# 640mk6.net
KiCad netlist of a schematic drawn in EAGLE
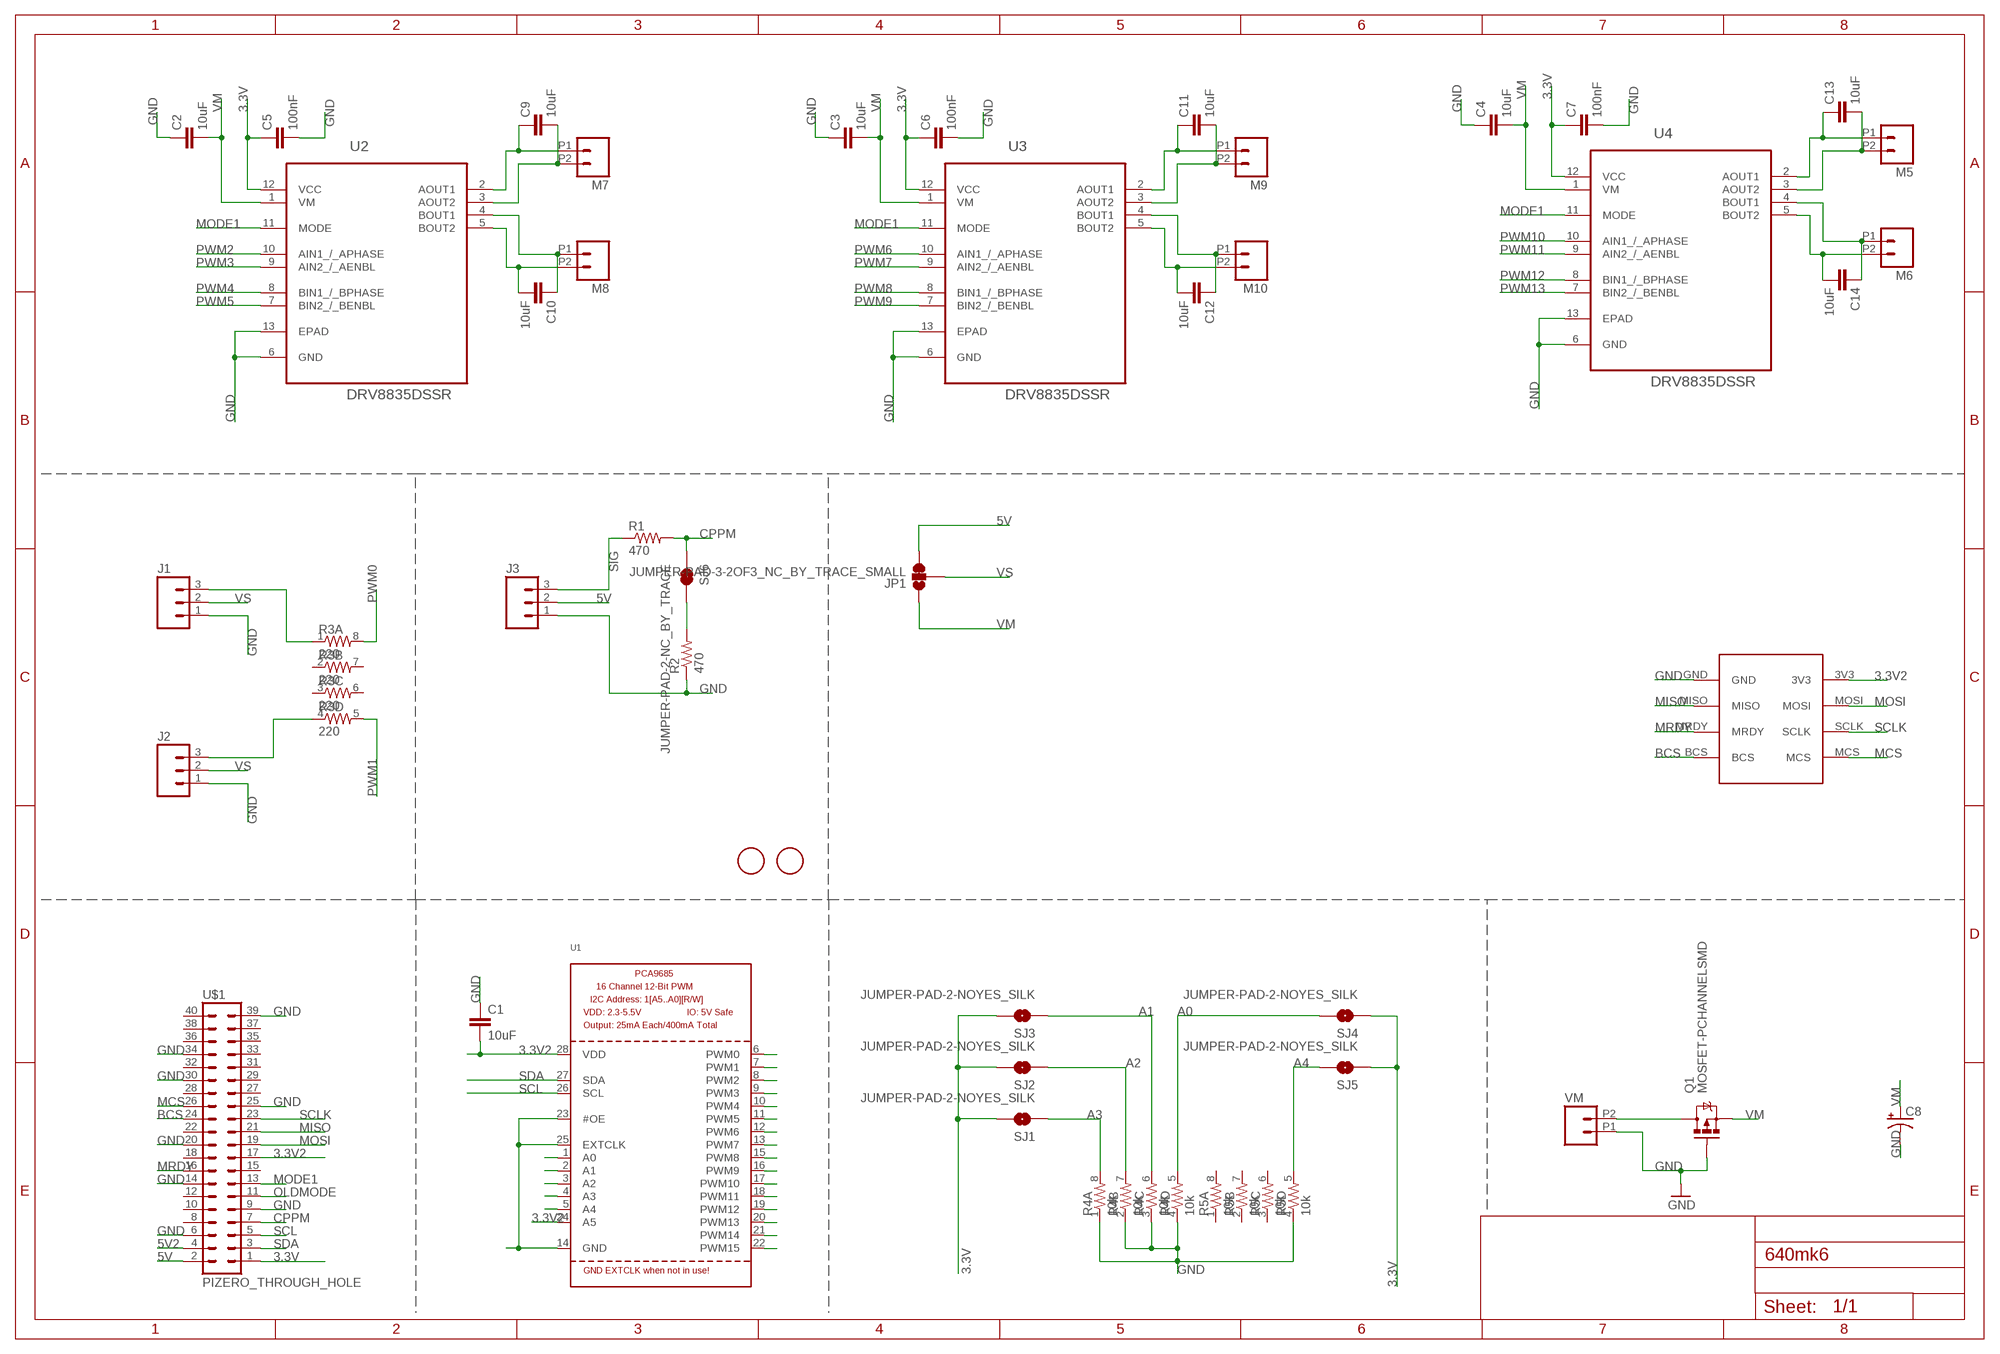
[diagram p0: schematic, sheet 1]

(export (version "E")
  (design (tool "Eeschema 10.0.6"))
  (components
    (comp (ref "C1")
      (value "10uF")
      (footprint "eagle-import:0805")
      (libsource (lib "eagle-import") (part "CAP0805"))
    )
    (comp (ref "C2")
      (value "10uF")
      (footprint "eagle-import:0805")
      (libsource (lib "eagle-import") (part "CAP0805"))
    )
    (comp (ref "C3")
      (value "10uF")
      (footprint "eagle-import:0805")
      (libsource (lib "eagle-import") (part "CAP0805"))
    )
    (comp (ref "C4")
      (value "10uF")
      (footprint "eagle-import:0805")
      (libsource (lib "eagle-import") (part "CAP0805"))
    )
    (comp (ref "C5")
      (value "100nF")
      (footprint "eagle-import:0805")
      (libsource (lib "eagle-import") (part "CAP0805"))
    )
    (comp (ref "C6")
      (value "100nF")
      (footprint "eagle-import:0805")
      (libsource (lib "eagle-import") (part "CAP0805"))
    )
    (comp (ref "C7")
      (value "100nF")
      (footprint "eagle-import:0805")
      (libsource (lib "eagle-import") (part "CAP0805"))
    )
    (comp (ref "C8")
      (value "CAP_POLPTH1")
      (footprint "eagle-import:CPOL-RADIAL-100UF-25V")
      (libsource (lib "eagle-import") (part "CAP_POLPTH1"))
    )
    (comp (ref "C9")
      (value "10uF")
      (footprint "eagle-import:0805")
      (libsource (lib "eagle-import") (part "CAP0805"))
    )
    (comp (ref "C10")
      (value "10uF")
      (footprint "eagle-import:0805")
      (libsource (lib "eagle-import") (part "CAP0805"))
    )
    (comp (ref "C11")
      (value "10uF")
      (footprint "eagle-import:0805")
      (libsource (lib "eagle-import") (part "CAP0805"))
    )
    (comp (ref "C12")
      (value "10uF")
      (footprint "eagle-import:0805")
      (libsource (lib "eagle-import") (part "CAP0805"))
    )
    (comp (ref "C13")
      (value "10uF")
      (footprint "eagle-import:0805")
      (libsource (lib "eagle-import") (part "CAP0805"))
    )
    (comp (ref "C14")
      (value "10uF")
      (footprint "eagle-import:0805")
      (libsource (lib "eagle-import") (part "CAP0805"))
    )
    (comp (ref "FID1")
      (value "FIDUCIAL")
      (footprint "eagle-import:FIDUCIAL_1MM")
      (libsource (lib "eagle-import") (part "FIDUCIAL"))
    )
    (comp (ref "FID2")
      (value "FIDUCIAL")
      (footprint "eagle-import:FIDUCIAL_1MM")
      (libsource (lib "eagle-import") (part "FIDUCIAL"))
    )
    (comp (ref "J1")
      (value "M03LOCK")
      (footprint "eagle-import:1X03_LOCK")
      (libsource (lib "eagle-import") (part "M03LOCK"))
    )
    (comp (ref "J2")
      (value "M03LOCK")
      (footprint "eagle-import:1X03_LOCK")
      (libsource (lib "eagle-import") (part "M03LOCK"))
    )
    (comp (ref "J3")
      (value "M03LOCK")
      (footprint "eagle-import:1X03_LOCK")
      (libsource (lib "eagle-import") (part "M03LOCK"))
    )
    (comp (ref "JP1")
      (value "JUMPER-PAD-3-2OF3_NC_BY_TRACE_SMALL")
      (footprint "eagle-import:PAD-JUMPER-3-2OF3_NC_BY_TRACE_YES_SILK_FULL_BOX")
      (libsource (lib "eagle-import") (part "JUMPER-PAD-3-2OF3_NC_BY_TRACE_SMALL"))
    )
    (comp (ref "M5")
      (value "M022.54MM_SCREWTERM")
      (footprint "eagle-import:1X02_2.54_SCREWTERM")
      (libsource (lib "eagle-import") (part "M022.54MM_SCREWTERM"))
    )
    (comp (ref "M6")
      (value "M022.54MM_SCREWTERM")
      (footprint "eagle-import:1X02_2.54_SCREWTERM")
      (libsource (lib "eagle-import") (part "M022.54MM_SCREWTERM"))
    )
    (comp (ref "M7")
      (value "M022.54MM_SCREWTERM")
      (footprint "eagle-import:1X02_2.54_SCREWTERM")
      (libsource (lib "eagle-import") (part "M022.54MM_SCREWTERM"))
    )
    (comp (ref "M8")
      (value "M022.54MM_SCREWTERM")
      (footprint "eagle-import:1X02_2.54_SCREWTERM")
      (libsource (lib "eagle-import") (part "M022.54MM_SCREWTERM"))
    )
    (comp (ref "M9")
      (value "M022.54MM_SCREWTERM")
      (footprint "eagle-import:1X02_2.54_SCREWTERM")
      (libsource (lib "eagle-import") (part "M022.54MM_SCREWTERM"))
    )
    (comp (ref "M10")
      (value "M022.54MM_SCREWTERM")
      (footprint "eagle-import:1X02_2.54_SCREWTERM")
      (libsource (lib "eagle-import") (part "M022.54MM_SCREWTERM"))
    )
    (comp (ref "Q1")
      (value "MOSFET-PCHANNELSMD")
      (footprint "eagle-import:SOT23-3")
      (libsource (lib "eagle-import") (part "MOSFET-PCHANNELSMD"))
    )
    (comp (ref "R1")
      (value "470")
      (footprint "eagle-import:0805")
      (libsource (lib "eagle-import") (part "RESISTOR0805-RES"))
    )
    (comp (ref "R2")
      (value "470")
      (footprint "eagle-import:0805")
      (libsource (lib "eagle-import") (part "RESISTOR0805-RES"))
    )
    (comp (ref "R3")
      (value "220")
      (footprint "eagle-import:0603-ARV")
      (libsource (lib "eagle-import") (part "RESISTOR-ARRAY0603-ARV"))
    )
    (comp (ref "R4")
      (value "10k")
      (footprint "eagle-import:0603-ARV")
      (libsource (lib "eagle-import") (part "RESISTOR-ARRAY0603-ARV"))
    )
    (comp (ref "R5")
      (value "10k")
      (footprint "eagle-import:0603-ARV")
      (libsource (lib "eagle-import") (part "RESISTOR-ARRAY0603-ARV"))
    )
    (comp (ref "SJ1")
      (value "JUMPER-PAD-2-NOYES_SILK")
      (footprint "eagle-import:PAD-JUMPER-2-NO_YES_SILK")
      (libsource (lib "eagle-import") (part "JUMPER-PAD-2-NOYES_SILK"))
    )
    (comp (ref "SJ2")
      (value "JUMPER-PAD-2-NOYES_SILK")
      (footprint "eagle-import:PAD-JUMPER-2-NO_YES_SILK")
      (libsource (lib "eagle-import") (part "JUMPER-PAD-2-NOYES_SILK"))
    )
    (comp (ref "SJ3")
      (value "JUMPER-PAD-2-NOYES_SILK")
      (footprint "eagle-import:PAD-JUMPER-2-NO_YES_SILK")
      (libsource (lib "eagle-import") (part "JUMPER-PAD-2-NOYES_SILK"))
    )
    (comp (ref "SJ4")
      (value "JUMPER-PAD-2-NOYES_SILK")
      (footprint "eagle-import:PAD-JUMPER-2-NO_YES_SILK")
      (libsource (lib "eagle-import") (part "JUMPER-PAD-2-NOYES_SILK"))
    )
    (comp (ref "SJ5")
      (value "JUMPER-PAD-2-NOYES_SILK")
      (footprint "eagle-import:PAD-JUMPER-2-NO_YES_SILK")
      (libsource (lib "eagle-import") (part "JUMPER-PAD-2-NOYES_SILK"))
    )
    (comp (ref "SJ6")
      (value "JUMPER-PAD-2-NC_BY_TRACE")
      (footprint "eagle-import:PAD-JUMPER-2-NC_BY_TRACE_YES_SILK")
      (libsource (lib "eagle-import") (part "JUMPER-PAD-2-NC_BY_TRACE"))
    )
    (comp (ref "U$1")
      (value "PIZERO_THROUGH_HOLE")
      (footprint "eagle-import:PIZERO_THOUGH_HOLE")
      (libsource (lib "eagle-import") (part "PIZERO_THROUGH_HOLE"))
    )
    (comp (ref "U$2")
      (value "2X4PADS")
      (footprint "eagle-import:2X4PADS")
      (libsource (lib "eagle-import") (part "2X4PADS"))
    )
    (comp (ref "U1")
      (value "PCA9685")
      (footprint "eagle-import:TSSOP28")
      (libsource (lib "eagle-import") (part "PCA9685"))
    )
    (comp (ref "U2")
      (value "DRV8835DSSR")
      (footprint "eagle-import:SON50P200X300X80-13N")
      (fields (field (name "MPN") "DRV8835DSSR "))
      (libsource (lib "eagle-import") (part "DRV8835DSSR"))
    )
    (comp (ref "U3")
      (value "DRV8835DSSR")
      (footprint "eagle-import:SON50P200X300X80-13N")
      (fields (field (name "MPN") "DRV8835DSSR "))
      (libsource (lib "eagle-import") (part "DRV8835DSSR"))
    )
    (comp (ref "U4")
      (value "DRV8835DSSR")
      (footprint "eagle-import:SON50P200X300X80-13N")
      (fields (field (name "MPN") "DRV8835DSSR "))
      (libsource (lib "eagle-import") (part "DRV8835DSSR"))
    )
    (comp (ref "VM")
      (value "M022.54MM_SCREWTERM")
      (footprint "eagle-import:1X02_2.54_SCREWTERM")
      (libsource (lib "eagle-import") (part "M022.54MM_SCREWTERM"))
    )
  )
  (nets
    (net (code "1") (name "/3.3V") (class "Default")
      (node (ref "C5") (pin "1") (pinfunction "1_1") (pintype "passive"))
      (node (ref "C6") (pin "1") (pinfunction "1_1") (pintype "passive"))
      (node (ref "C7") (pin "1") (pinfunction "1_1") (pintype "passive"))
      (node (ref "SJ1") (pin "2") (pinfunction "2_2") (pintype "passive"))
      (node (ref "SJ2") (pin "2") (pinfunction "2_2") (pintype "passive"))
      (node (ref "SJ3") (pin "2") (pinfunction "2_2") (pintype "passive"))
      (node (ref "SJ4") (pin "1") (pinfunction "1_1") (pintype "passive"))
      (node (ref "SJ5") (pin "1") (pinfunction "1_1") (pintype "passive"))
      (node (ref "U$1") (pin "1") (pinfunction "1_1") (pintype "passive"))
      (node (ref "U2") (pin "12") (pinfunction "VCC_12") (pintype "power_in"))
      (node (ref "U3") (pin "12") (pinfunction "VCC_12") (pintype "power_in"))
      (node (ref "U4") (pin "12") (pinfunction "VCC_12") (pintype "power_in"))
    )
    (net (code "2") (name "/3.3V2") (class "Default")
      (node (ref "C1") (pin "2") (pinfunction "2_2") (pintype "passive"))
      (node (ref "U$1") (pin "17") (pinfunction "17_17") (pintype "passive"))
      (node (ref "U$2") (pin "3V3") (pinfunction "3V3_3V3") (pintype "bidirectional"))
      (node (ref "U1") (pin "24") (pinfunction "A5_24") (pintype "bidirectional"))
      (node (ref "U1") (pin "28") (pinfunction "VDD_28") (pintype "power_in"))
    )
    (net (code "3") (name "/5V") (class "Default")
      (node (ref "J3") (pin "2") (pinfunction "2_2") (pintype "passive"))
      (node (ref "JP1") (pin "3") (pinfunction "3_3") (pintype "passive"))
      (node (ref "U$1") (pin "2") (pinfunction "2_2") (pintype "passive"))
    )
    (net (code "4") (name "/5V2") (class "Default")
      (node (ref "U$1") (pin "4") (pinfunction "4_4") (pintype "passive"))
    )
    (net (code "5") (name "/A0") (class "Default")
      (node (ref "R4") (pin "5") (pinfunction "2_5") (pintype "passive"))
      (node (ref "SJ4") (pin "2") (pinfunction "2_2") (pintype "passive"))
      (node (ref "U1") (pin "1") (pinfunction "A0_1") (pintype "bidirectional"))
    )
    (net (code "6") (name "/A1") (class "Default")
      (node (ref "R4") (pin "6") (pinfunction "2_6") (pintype "passive"))
      (node (ref "SJ3") (pin "1") (pinfunction "1_1") (pintype "passive"))
      (node (ref "U1") (pin "2") (pinfunction "A1_2") (pintype "bidirectional"))
    )
    (net (code "7") (name "/A2") (class "Default")
      (node (ref "R4") (pin "7") (pinfunction "2_7") (pintype "passive"))
      (node (ref "SJ2") (pin "1") (pinfunction "1_1") (pintype "passive"))
      (node (ref "U1") (pin "3") (pinfunction "A2_3") (pintype "bidirectional"))
    )
    (net (code "8") (name "/A3") (class "Default")
      (node (ref "R4") (pin "8") (pinfunction "2_8") (pintype "passive"))
      (node (ref "SJ1") (pin "1") (pinfunction "1_1") (pintype "passive"))
      (node (ref "U1") (pin "4") (pinfunction "A3_4") (pintype "bidirectional"))
    )
    (net (code "9") (name "/A4") (class "Default")
      (node (ref "R5") (pin "5") (pinfunction "2_5") (pintype "passive"))
      (node (ref "SJ5") (pin "2") (pinfunction "2_2") (pintype "passive"))
      (node (ref "U1") (pin "5") (pinfunction "A4_5") (pintype "bidirectional"))
    )
    (net (code "10") (name "/BCS") (class "Default")
      (node (ref "U$1") (pin "24") (pinfunction "24_24") (pintype "passive"))
      (node (ref "U$2") (pin "BCS") (pinfunction "BCS_BCS") (pintype "bidirectional"))
    )
    (net (code "11") (name "/CPPM") (class "Default")
      (node (ref "R1") (pin "2") (pinfunction "2_2") (pintype "passive"))
      (node (ref "SJ6") (pin "1") (pinfunction "1_1") (pintype "passive"))
      (node (ref "U$1") (pin "7") (pinfunction "7_7") (pintype "passive"))
    )
    (net (code "12") (name "/MCS") (class "Default")
      (node (ref "U$1") (pin "26") (pinfunction "26_26") (pintype "passive"))
      (node (ref "U$2") (pin "MCS") (pinfunction "MCS_MCS") (pintype "bidirectional"))
    )
    (net (code "13") (name "/MISO") (class "Default")
      (node (ref "U$1") (pin "21") (pinfunction "21_21") (pintype "passive"))
      (node (ref "U$2") (pin "MISO") (pinfunction "MISO_MISO") (pintype "bidirectional"))
    )
    (net (code "14") (name "/MODE1") (class "Default")
      (node (ref "U$1") (pin "13") (pinfunction "13_13") (pintype "passive"))
      (node (ref "U2") (pin "11") (pinfunction "MODE_11") (pintype "input"))
      (node (ref "U3") (pin "11") (pinfunction "MODE_11") (pintype "input"))
      (node (ref "U4") (pin "11") (pinfunction "MODE_11") (pintype "input"))
    )
    (net (code "15") (name "/MOSI") (class "Default")
      (node (ref "U$1") (pin "19") (pinfunction "19_19") (pintype "passive"))
      (node (ref "U$2") (pin "MOSI") (pinfunction "MOSI_MOSI") (pintype "bidirectional"))
    )
    (net (code "16") (name "/MRDY") (class "Default")
      (node (ref "U$1") (pin "16") (pinfunction "16_16") (pintype "passive"))
      (node (ref "U$2") (pin "MRDY") (pinfunction "MRDY_MRDY") (pintype "bidirectional"))
    )
    (net (code "17") (name "/OLDMODE") (class "Default")
      (node (ref "U$1") (pin "11") (pinfunction "11_11") (pintype "passive"))
    )
    (net (code "18") (name "/PWM0") (class "Default")
      (node (ref "R3") (pin "8") (pinfunction "2_8") (pintype "passive"))
      (node (ref "U1") (pin "6") (pinfunction "PWM0_6") (pintype "output"))
    )
    (net (code "19") (name "/PWM1") (class "Default")
      (node (ref "R3") (pin "5") (pinfunction "2_5") (pintype "passive"))
      (node (ref "U1") (pin "7") (pinfunction "PWM1_7") (pintype "output"))
    )
    (net (code "20") (name "/PWM2") (class "Default")
      (node (ref "U1") (pin "8") (pinfunction "PWM2_8") (pintype "output"))
      (node (ref "U2") (pin "10") (pinfunction "AIN1_/_APHASE_10") (pintype "input"))
    )
    (net (code "21") (name "/PWM3") (class "Default")
      (node (ref "U1") (pin "9") (pinfunction "PWM3_9") (pintype "output"))
      (node (ref "U2") (pin "9") (pinfunction "AIN2_/_AENBL_9") (pintype "input"))
    )
    (net (code "22") (name "/PWM4") (class "Default")
      (node (ref "U1") (pin "10") (pinfunction "PWM4_10") (pintype "output"))
      (node (ref "U2") (pin "8") (pinfunction "BIN1_/_BPHASE_8") (pintype "input"))
    )
    (net (code "23") (name "/PWM5") (class "Default")
      (node (ref "U1") (pin "11") (pinfunction "PWM5_11") (pintype "output"))
      (node (ref "U2") (pin "7") (pinfunction "BIN2_/_BENBL_7") (pintype "input"))
    )
    (net (code "24") (name "/PWM6") (class "Default")
      (node (ref "U1") (pin "12") (pinfunction "PWM6_12") (pintype "output"))
      (node (ref "U3") (pin "10") (pinfunction "AIN1_/_APHASE_10") (pintype "input"))
    )
    (net (code "25") (name "/PWM7") (class "Default")
      (node (ref "U1") (pin "13") (pinfunction "PWM7_13") (pintype "output"))
      (node (ref "U3") (pin "9") (pinfunction "AIN2_/_AENBL_9") (pintype "input"))
    )
    (net (code "26") (name "/PWM8") (class "Default")
      (node (ref "U1") (pin "15") (pinfunction "PWM8_15") (pintype "output"))
      (node (ref "U3") (pin "8") (pinfunction "BIN1_/_BPHASE_8") (pintype "input"))
    )
    (net (code "27") (name "/PWM9") (class "Default")
      (node (ref "U1") (pin "16") (pinfunction "PWM9_16") (pintype "output"))
      (node (ref "U3") (pin "7") (pinfunction "BIN2_/_BENBL_7") (pintype "input"))
    )
    (net (code "28") (name "/PWM10") (class "Default")
      (node (ref "U1") (pin "17") (pinfunction "PWM10_17") (pintype "output"))
      (node (ref "U4") (pin "10") (pinfunction "AIN1_/_APHASE_10") (pintype "input"))
    )
    (net (code "29") (name "/PWM11") (class "Default")
      (node (ref "U1") (pin "18") (pinfunction "PWM11_18") (pintype "output"))
      (node (ref "U4") (pin "9") (pinfunction "AIN2_/_AENBL_9") (pintype "input"))
    )
    (net (code "30") (name "/PWM12") (class "Default")
      (node (ref "U1") (pin "19") (pinfunction "PWM12_19") (pintype "output"))
      (node (ref "U4") (pin "8") (pinfunction "BIN1_/_BPHASE_8") (pintype "input"))
    )
    (net (code "31") (name "/PWM13") (class "Default")
      (node (ref "U1") (pin "20") (pinfunction "PWM13_20") (pintype "output"))
      (node (ref "U4") (pin "7") (pinfunction "BIN2_/_BENBL_7") (pintype "input"))
    )
    (net (code "32") (name "/SCL") (class "Default")
      (node (ref "U$1") (pin "5") (pinfunction "5_5") (pintype "passive"))
      (node (ref "U1") (pin "26") (pinfunction "SCL_26") (pintype "bidirectional"))
    )
    (net (code "33") (name "/SCLK") (class "Default")
      (node (ref "U$1") (pin "23") (pinfunction "23_23") (pintype "passive"))
      (node (ref "U$2") (pin "SCLK") (pinfunction "SCLK_SCLK") (pintype "bidirectional"))
    )
    (net (code "34") (name "/SDA") (class "Default")
      (node (ref "U$1") (pin "3") (pinfunction "3_3") (pintype "passive"))
      (node (ref "U1") (pin "27") (pinfunction "SDA_27") (pintype "bidirectional"))
    )
    (net (code "35") (name "/SIG") (class "Default")
      (node (ref "J3") (pin "3") (pinfunction "3_3") (pintype "passive"))
      (node (ref "R1") (pin "1") (pinfunction "1_1") (pintype "passive"))
    )
    (net (code "36") (name "/VM") (class "Default")
      (node (ref "C2") (pin "2") (pinfunction "2_2") (pintype "passive"))
      (node (ref "C3") (pin "2") (pinfunction "2_2") (pintype "passive"))
      (node (ref "C4") (pin "2") (pinfunction "2_2") (pintype "passive"))
      (node (ref "C8") (pin "1") (pinfunction "+_1") (pintype "passive"))
      (node (ref "JP1") (pin "1") (pinfunction "1_1") (pintype "passive"))
      (node (ref "Q1") (pin "2") (pinfunction "S_2") (pintype "passive"))
      (node (ref "U2") (pin "1") (pinfunction "VM_1") (pintype "power_in"))
      (node (ref "U3") (pin "1") (pinfunction "VM_1") (pintype "power_in"))
      (node (ref "U4") (pin "1") (pinfunction "VM_1") (pintype "power_in"))
    )
    (net (code "37") (name "/VS") (class "Default")
      (node (ref "J1") (pin "2") (pinfunction "2_2") (pintype "passive"))
      (node (ref "J2") (pin "2") (pinfunction "2_2") (pintype "passive"))
      (node (ref "JP1") (pin "2") (pinfunction "2_2") (pintype "passive"))
    )
    (net (code "38") (name "GND") (class "Default")
      (node (ref "C1") (pin "1") (pinfunction "1_1") (pintype "passive"))
      (node (ref "C2") (pin "1") (pinfunction "1_1") (pintype "passive"))
      (node (ref "C3") (pin "1") (pinfunction "1_1") (pintype "passive"))
      (node (ref "C4") (pin "1") (pinfunction "1_1") (pintype "passive"))
      (node (ref "C5") (pin "2") (pinfunction "2_2") (pintype "passive"))
      (node (ref "C6") (pin "2") (pinfunction "2_2") (pintype "passive"))
      (node (ref "C7") (pin "2") (pinfunction "2_2") (pintype "passive"))
      (node (ref "C8") (pin "2") (pinfunction "-_2") (pintype "passive"))
      (node (ref "J1") (pin "1") (pinfunction "1_1") (pintype "passive"))
      (node (ref "J2") (pin "1") (pinfunction "1_1") (pintype "passive"))
      (node (ref "J3") (pin "1") (pinfunction "1_1") (pintype "passive"))
      (node (ref "Q1") (pin "1") (pinfunction "G_1") (pintype "passive"))
      (node (ref "R2") (pin "1") (pinfunction "1_1") (pintype "passive"))
      (node (ref "R4") (pin "1") (pinfunction "1_1") (pintype "passive"))
      (node (ref "R4") (pin "2") (pinfunction "1_2") (pintype "passive"))
      (node (ref "R4") (pin "3") (pinfunction "1_3") (pintype "passive"))
      (node (ref "R4") (pin "4") (pinfunction "1_4") (pintype "passive"))
      (node (ref "R5") (pin "4") (pinfunction "1_4") (pintype "passive"))
      (node (ref "U$1") (pin "14") (pinfunction "14_14") (pintype "passive"))
      (node (ref "U$1") (pin "20") (pinfunction "20_20") (pintype "passive"))
      (node (ref "U$1") (pin "25") (pinfunction "25_25") (pintype "passive"))
      (node (ref "U$1") (pin "30") (pinfunction "30_30") (pintype "passive"))
      (node (ref "U$1") (pin "34") (pinfunction "34_34") (pintype "passive"))
      (node (ref "U$1") (pin "39") (pinfunction "39_39") (pintype "passive"))
      (node (ref "U$1") (pin "6") (pinfunction "6_6") (pintype "passive"))
      (node (ref "U$1") (pin "9") (pinfunction "9_9") (pintype "passive"))
      (node (ref "U$2") (pin "GND") (pinfunction "GND_GND") (pintype "bidirectional"))
      (node (ref "U1") (pin "14") (pinfunction "GND_14") (pintype "power_in"))
      (node (ref "U1") (pin "23") (pinfunction "#OE_23") (pintype "input"))
      (node (ref "U1") (pin "25") (pinfunction "EXTCLK_25") (pintype "input"))
      (node (ref "U2") (pin "13") (pinfunction "EPAD_13") (pintype "passive"))
      (node (ref "U2") (pin "6") (pinfunction "GND_6") (pintype "passive"))
      (node (ref "U3") (pin "13") (pinfunction "EPAD_13") (pintype "passive"))
      (node (ref "U3") (pin "6") (pinfunction "GND_6") (pintype "passive"))
      (node (ref "U4") (pin "13") (pinfunction "EPAD_13") (pintype "passive"))
      (node (ref "U4") (pin "6") (pinfunction "GND_6") (pintype "passive"))
      (node (ref "VM") (pin "P1") (pinfunction "1_P1") (pintype "passive"))
    )
    (net (code "39") (name "Net-(J1-Pad3)") (class "Default")
      (node (ref "J1") (pin "3") (pinfunction "3_3") (pintype "passive"))
      (node (ref "R3") (pin "1") (pinfunction "1_1") (pintype "passive"))
    )
    (net (code "40") (name "Net-(M5-1)") (class "Default")
      (node (ref "C13") (pin "1") (pinfunction "1_1") (pintype "passive"))
      (node (ref "M5") (pin "P1") (pinfunction "1_P1") (pintype "passive"))
      (node (ref "U4") (pin "2") (pinfunction "AOUT1_2") (pintype "output"))
    )
    (net (code "41") (name "Net-(M5-2)") (class "Default")
      (node (ref "C13") (pin "2") (pinfunction "2_2") (pintype "passive"))
      (node (ref "M5") (pin "P2") (pinfunction "2_P2") (pintype "passive"))
      (node (ref "U4") (pin "3") (pinfunction "AOUT2_3") (pintype "output"))
    )
    (net (code "42") (name "Net-(M6-1)") (class "Default")
      (node (ref "C14") (pin "1") (pinfunction "1_1") (pintype "passive"))
      (node (ref "M6") (pin "P1") (pinfunction "1_P1") (pintype "passive"))
      (node (ref "U4") (pin "4") (pinfunction "BOUT1_4") (pintype "output"))
    )
    (net (code "43") (name "Net-(M6-2)") (class "Default")
      (node (ref "C14") (pin "2") (pinfunction "2_2") (pintype "passive"))
      (node (ref "M6") (pin "P2") (pinfunction "2_P2") (pintype "passive"))
      (node (ref "U4") (pin "5") (pinfunction "BOUT2_5") (pintype "output"))
    )
    (net (code "44") (name "Net-(M7-1)") (class "Default")
      (node (ref "C9") (pin "1") (pinfunction "1_1") (pintype "passive"))
      (node (ref "M7") (pin "P1") (pinfunction "1_P1") (pintype "passive"))
      (node (ref "U2") (pin "2") (pinfunction "AOUT1_2") (pintype "output"))
    )
    (net (code "45") (name "Net-(M7-2)") (class "Default")
      (node (ref "C9") (pin "2") (pinfunction "2_2") (pintype "passive"))
      (node (ref "M7") (pin "P2") (pinfunction "2_P2") (pintype "passive"))
      (node (ref "U2") (pin "3") (pinfunction "AOUT2_3") (pintype "output"))
    )
    (net (code "46") (name "Net-(M8-1)") (class "Default")
      (node (ref "C10") (pin "1") (pinfunction "1_1") (pintype "passive"))
      (node (ref "M8") (pin "P1") (pinfunction "1_P1") (pintype "passive"))
      (node (ref "U2") (pin "4") (pinfunction "BOUT1_4") (pintype "output"))
    )
    (net (code "47") (name "Net-(M8-2)") (class "Default")
      (node (ref "C10") (pin "2") (pinfunction "2_2") (pintype "passive"))
      (node (ref "M8") (pin "P2") (pinfunction "2_P2") (pintype "passive"))
      (node (ref "U2") (pin "5") (pinfunction "BOUT2_5") (pintype "output"))
    )
    (net (code "48") (name "Net-(M9-1)") (class "Default")
      (node (ref "C11") (pin "1") (pinfunction "1_1") (pintype "passive"))
      (node (ref "M9") (pin "P1") (pinfunction "1_P1") (pintype "passive"))
      (node (ref "U3") (pin "2") (pinfunction "AOUT1_2") (pintype "output"))
    )
    (net (code "49") (name "Net-(M9-2)") (class "Default")
      (node (ref "C11") (pin "2") (pinfunction "2_2") (pintype "passive"))
      (node (ref "M9") (pin "P2") (pinfunction "2_P2") (pintype "passive"))
      (node (ref "U3") (pin "3") (pinfunction "AOUT2_3") (pintype "output"))
    )
    (net (code "50") (name "Net-(M10-1)") (class "Default")
      (node (ref "C12") (pin "1") (pinfunction "1_1") (pintype "passive"))
      (node (ref "M10") (pin "P1") (pinfunction "1_P1") (pintype "passive"))
      (node (ref "U3") (pin "4") (pinfunction "BOUT1_4") (pintype "output"))
    )
    (net (code "51") (name "Net-(M10-2)") (class "Default")
      (node (ref "C12") (pin "2") (pinfunction "2_2") (pintype "passive"))
      (node (ref "M10") (pin "P2") (pinfunction "2_P2") (pintype "passive"))
      (node (ref "U3") (pin "5") (pinfunction "BOUT2_5") (pintype "output"))
    )
    (net (code "52") (name "Net-(Q1-D)") (class "Default")
      (node (ref "Q1") (pin "3") (pinfunction "D_3") (pintype "passive"))
      (node (ref "VM") (pin "P2") (pinfunction "2_P2") (pintype "passive"))
    )
    (net (code "53") (name "Net-(R2-Pad2)") (class "Default")
      (node (ref "R2") (pin "2") (pinfunction "2_2") (pintype "passive"))
      (node (ref "SJ6") (pin "2") (pinfunction "2_2") (pintype "passive"))
    )
    (net (code "54") (name "Net-(R3D-1)") (class "Default")
      (node (ref "J2") (pin "3") (pinfunction "3_3") (pintype "passive"))
      (node (ref "R3") (pin "4") (pinfunction "1_4") (pintype "passive"))
    )
    (net (code "55") (name "unconnected-(R3B-1-Pad2)") (class "Default")
      (node (ref "R3") (pin "2") (pinfunction "1_2") (pintype "passive"))
    )
    (net (code "56") (name "unconnected-(R3B-2-Pad7)") (class "Default")
      (node (ref "R3") (pin "7") (pinfunction "2_7") (pintype "passive"))
    )
    (net (code "57") (name "unconnected-(R3C-1-Pad3)") (class "Default")
      (node (ref "R3") (pin "3") (pinfunction "1_3") (pintype "passive"))
    )
    (net (code "58") (name "unconnected-(R3C-2-Pad6)") (class "Default")
      (node (ref "R3") (pin "6") (pinfunction "2_6") (pintype "passive"))
    )
    (net (code "59") (name "unconnected-(R5-Pad1)") (class "Default")
      (node (ref "R5") (pin "1") (pinfunction "1_1") (pintype "passive"))
    )
    (net (code "60") (name "unconnected-(R5A-2-Pad8)") (class "Default")
      (node (ref "R5") (pin "8") (pinfunction "2_8") (pintype "passive"))
    )
    (net (code "61") (name "unconnected-(R5B-1-Pad2)") (class "Default")
      (node (ref "R5") (pin "2") (pinfunction "1_2") (pintype "passive"))
    )
    (net (code "62") (name "unconnected-(R5B-2-Pad7)") (class "Default")
      (node (ref "R5") (pin "7") (pinfunction "2_7") (pintype "passive"))
    )
    (net (code "63") (name "unconnected-(R5C-1-Pad3)") (class "Default")
      (node (ref "R5") (pin "3") (pinfunction "1_3") (pintype "passive"))
    )
    (net (code "64") (name "unconnected-(R5C-2-Pad6)") (class "Default")
      (node (ref "R5") (pin "6") (pinfunction "2_6") (pintype "passive"))
    )
    (net (code "65") (name "unconnected-(U$1-Pad8)") (class "Default")
      (node (ref "U$1") (pin "8") (pinfunction "8_8") (pintype "passive"))
    )
    (net (code "66") (name "unconnected-(U$1-Pad10)") (class "Default")
      (node (ref "U$1") (pin "10") (pinfunction "10_10") (pintype "passive"))
    )
    (net (code "67") (name "unconnected-(U$1-Pad12)") (class "Default")
      (node (ref "U$1") (pin "12") (pinfunction "12_12") (pintype "passive"))
    )
    (net (code "68") (name "unconnected-(U$1-Pad15)") (class "Default")
      (node (ref "U$1") (pin "15") (pinfunction "15_15") (pintype "passive"))
    )
    (net (code "69") (name "unconnected-(U$1-Pad18)") (class "Default")
      (node (ref "U$1") (pin "18") (pinfunction "18_18") (pintype "passive"))
    )
    (net (code "70") (name "unconnected-(U$1-Pad22)") (class "Default")
      (node (ref "U$1") (pin "22") (pinfunction "22_22") (pintype "passive"))
    )
    (net (code "71") (name "unconnected-(U$1-Pad27)") (class "Default")
      (node (ref "U$1") (pin "27") (pinfunction "27_27") (pintype "passive"))
    )
    (net (code "72") (name "unconnected-(U$1-Pad28)") (class "Default")
      (node (ref "U$1") (pin "28") (pinfunction "28_28") (pintype "passive"))
    )
    (net (code "73") (name "unconnected-(U$1-Pad29)") (class "Default")
      (node (ref "U$1") (pin "29") (pinfunction "29_29") (pintype "passive"))
    )
    (net (code "74") (name "unconnected-(U$1-Pad31)") (class "Default")
      (node (ref "U$1") (pin "31") (pinfunction "31_31") (pintype "passive"))
    )
    (net (code "75") (name "unconnected-(U$1-Pad32)") (class "Default")
      (node (ref "U$1") (pin "32") (pinfunction "32_32") (pintype "passive"))
    )
    (net (code "76") (name "unconnected-(U$1-Pad33)") (class "Default")
      (node (ref "U$1") (pin "33") (pinfunction "33_33") (pintype "passive"))
    )
    (net (code "77") (name "unconnected-(U$1-Pad35)") (class "Default")
      (node (ref "U$1") (pin "35") (pinfunction "35_35") (pintype "passive"))
    )
    (net (code "78") (name "unconnected-(U$1-Pad36)") (class "Default")
      (node (ref "U$1") (pin "36") (pinfunction "36_36") (pintype "passive"))
    )
    (net (code "79") (name "unconnected-(U$1-Pad37)") (class "Default")
      (node (ref "U$1") (pin "37") (pinfunction "37_37") (pintype "passive"))
    )
    (net (code "80") (name "unconnected-(U$1-Pad38)") (class "Default")
      (node (ref "U$1") (pin "38") (pinfunction "38_38") (pintype "passive"))
    )
    (net (code "81") (name "unconnected-(U$1-Pad40)") (class "Default")
      (node (ref "U$1") (pin "40") (pinfunction "40_40") (pintype "passive"))
    )
    (net (code "82") (name "unconnected-(U1-PWM14-Pad21)") (class "Default")
      (node (ref "U1") (pin "21") (pinfunction "PWM14_21") (pintype "output"))
    )
    (net (code "83") (name "unconnected-(U1-PWM15-Pad22)") (class "Default")
      (node (ref "U1") (pin "22") (pinfunction "PWM15_22") (pintype "output"))
    )
  )
)
